# Power.net
KiCad netlist of a schematic drawn in Altium Designer
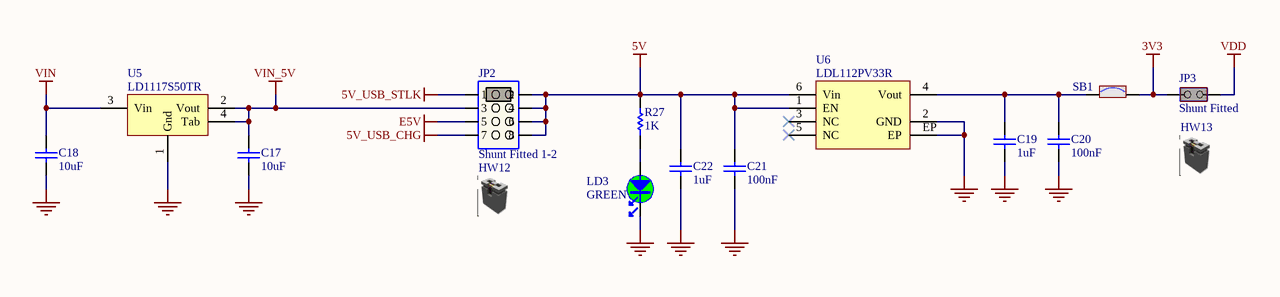
[diagram p0: Power.SchDoc]

(export (version "E")
  (design (tool "Eeschema 10.0.6"))
  (components
    (comp (ref "C17")
      (value "10uF")
      (footprint "C0805")
      (description "Capacitor, MLCC, 10uF, 25V, X5R, 10%, 0805, T=0,85mm")
      (fields
        (field (name "INTERNAL_PART_NUMBER") "MCD-00014")
        (field (name "MANUFACTURER_PART_NUMBER") "CC0805KRX5R8BB106")
        (field (name "PROVIDED_BY") "Subcon")
      )
      (libsource (lib "MCD_PARTS_database") (part "Capacitor"))
    )
    (comp (ref "C18")
      (value "10uF")
      (footprint "C0805")
      (description "Capacitor, MLCC, 10uF, 25V, X5R, 10%, 0805, T=0,85mm")
      (fields
        (field (name "INTERNAL_PART_NUMBER") "MCD-00014")
        (field (name "MANUFACTURER_PART_NUMBER") "CC0805KRX5R8BB106")
        (field (name "PROVIDED_BY") "Subcon")
      )
      (libsource (lib "MCD_PARTS_database") (part "Capacitor"))
    )
    (comp (ref "C19")
      (value "1uF")
      (footprint "C0603")
      (description "Capacitor, MLCC, 1uF, 16V, X5R, 10%, 0603, T=0,8mm")
      (fields
        (field (name "INTERNAL_PART_NUMBER") "MCD-00010")
        (field (name "MANUFACTURER_PART_NUMBER") "CC0603KRX5R7BB105")
        (field (name "PROVIDED_BY") "Subcon")
      )
      (libsource (lib "MCD_PARTS_database") (part "Capacitor"))
    )
    (comp (ref "C20")
      (value "100nF")
      (footprint "C0603")
      (description "Capacitor, MLCC, 100nF, 16V, X7R, 10%, 0603, T=0,8mm")
      (fields
        (field (name "INTERNAL_PART_NUMBER") "MCD-00211")
        (field (name "MANUFACTURER_PART_NUMBER") "CC0603KRX7R7BB104")
        (field (name "PROVIDED_BY") "Subcon")
      )
      (libsource (lib "MCD_PARTS_database") (part "Capacitor"))
    )
    (comp (ref "C21")
      (value "100nF")
      (footprint "C0603")
      (description "Capacitor, MLCC, 100nF, 16V, X7R, 10%, 0603, T=0,8mm")
      (fields
        (field (name "INTERNAL_PART_NUMBER") "MCD-00211")
        (field (name "MANUFACTURER_PART_NUMBER") "CC0603KRX7R7BB104")
        (field (name "PROVIDED_BY") "Subcon")
      )
      (libsource (lib "MCD_PARTS_database") (part "Capacitor"))
    )
    (comp (ref "C22")
      (value "1uF")
      (footprint "C0603")
      (description "Capacitor, MLCC, 1uF, 16V, X5R, 10%, 0603, T=0,8mm")
      (fields
        (field (name "INTERNAL_PART_NUMBER") "MCD-00010")
        (field (name "MANUFACTURER_PART_NUMBER") "CC0603KRX5R7BB105")
        (field (name "PROVIDED_BY") "Subcon")
      )
      (libsource (lib "MCD_PARTS_database") (part "Capacitor"))
    )
    (comp (ref "HW12")
      (value "Shunt 2.54mm")
      (footprint "N/A")
      (description "SHUNT 2.54mm BLACK")
      (fields
        (field (name "INTERNAL_PART_NUMBER") "MCD-00043")
        (field (name "MANUFACTURER_PART_NUMBER") "SNT-100-BK-G")
        (field (name "PROVIDED_BY") "Subcon")
      )
      (libsource (lib "MCD_PARTS_database") (part "Shunt 2.54mm"))
    )
    (comp (ref "HW13")
      (value "Shunt 2.54mm")
      (footprint "N/A")
      (description "SHUNT 2.54mm BLACK")
      (fields
        (field (name "INTERNAL_PART_NUMBER") "MCD-00043")
        (field (name "MANUFACTURER_PART_NUMBER") "SNT-100-BK-G")
        (field (name "PROVIDED_BY") "Subcon")
      )
      (libsource (lib "MCD_PARTS_database") (part "Shunt 2.54mm"))
    )
    (comp (ref "JP2")
      (value "Shunt Fitted 1-2")
      (footprint "CON_SAMTEC_TSW-104-07-X-D")
      (description "Header, 4x2, 2,54mm, VR, TH, Height 5.84mm/2.54mm - Shunt Fitted 1-2")
      (fields
        (field (name "INTERNAL_PART_NUMBER") "MCD-00686")
        (field (name "MANUFACTURER_PART_NUMBER") "TSW-104-07-x-D")
        (field (name "PROVIDED_BY") "Subcon")
      )
      (libsource (lib "MCD_PARTS_database") (part "Jumper_Header 4x2 Fitted 1-2"))
    )
    (comp (ref "JP3")
      (value "Shunt Fitted")
      (footprint "CON_SAMTEC_TSW-102-07-G-S")
      (description "Header, 2x1, 2,54mm, VR, TH, Height 5.84mm/2.54mm - Shunt Fitted by default")
      (fields
        (field (name "INTERNAL_PART_NUMBER") "MCD-00683")
        (field (name "MANUFACTURER_PART_NUMBER") "TSW-102-07-x-S")
        (field (name "PROVIDED_BY") "Subcon")
      )
      (libsource (lib "MCD_PARTS_database") (part "Jumper_Header 2x1 Fitted"))
    )
    (comp (ref "LD3")
      (value "GREEN")
      (footprint "LED_0603_GREEN")
      (description "LED, Green, 0603")
      (fields
        (field (name "INTERNAL_PART_NUMBER") "MCD-00050")
        (field (name "MANUFACTURER_PART_NUMBER") "19-213SYGC/S530-E2/TR8")
        (field (name "PROVIDED_BY") "Subcon")
      )
      (libsource (lib "MCD_PARTS_database") (part "LED_green"))
    )
    (comp (ref "R27")
      (value "1K")
      (footprint "R0603")
      (description "Resistor,1K,0603,1%,1/10W")
      (fields
        (field (name "INTERNAL_PART_NUMBER") "MCD-00070")
        (field (name "MANUFACTURER_PART_NUMBER") "RC0603FR-071KL")
        (field (name "PROVIDED_BY") "Subcon")
      )
      (libsource (lib "MCD_PARTS_database") (part "Resistor"))
    )
    (comp (ref "SB1")
      (value "SB_ON")
      (footprint "SOLDER-BRIDGE_R0603-0R")
      (description "Solder Bridge ON")
      (fields (field (name "INTERNAL_PART_NUMBER") "MCD-00071") (field (name "PROVIDED_BY") "Subcon"))
      (libsource (lib "MCD_PARTS_database") (part "SB_ON"))
    )
    (comp (ref "U5")
      (value "LD1117S50TR")
      (footprint "REG_SOT223-TAB")
      (description "IC REG LDO 5V 0.8A SOT223")
      (fields
        (field (name "INTERNAL_PART_NUMBER") "MCD-00088")
        (field (name "MANUFACTURER") "STMICROELECTRONICS")
        (field (name "PROVIDED_BY") "Subcon")
      )
      (libsource (lib "MCD_PARTS_database") (part "LD1117S50TR"))
    )
    (comp (ref "U6")
      (value "LDL112PV33R")
      (footprint "ICC_DFN6-EPAD_3X3_P095")
      (description "1.2 A low quiescent current LDO with reverse current protection")
      (fields
        (field (name "INTERNAL_PART_NUMBER") "MCD-00664")
        (field (name "MANUFACTURER") "STMICROELECTRONICS")
        (field (name "PROVIDED_BY") "Subcon")
      )
      (libsource (lib "MCD_PARTS_database") (part "LDL112PV33R"))
    )
  )
  (nets
    (net (code "1") (name "3V3") (class "Default")
      (node (ref "JP3") (pin "2") (pinfunction "NO_2") (pintype "passive"))
      (node (ref "SB1") (pin "2") (pinfunction "2_2") (pintype "passive"))
    )
    (net (code "2") (name "5V") (class "Default")
      (node (ref "C21") (pin "2") (pinfunction "2_2") (pintype "passive"))
      (node (ref "C22") (pin "2") (pinfunction "2_2") (pintype "passive"))
      (node (ref "JP2") (pin "2") (pinfunction "2_2") (pintype "passive"))
      (node (ref "JP2") (pin "4") (pinfunction "4_4") (pintype "passive"))
      (node (ref "JP2") (pin "6") (pinfunction "6_6") (pintype "passive"))
      (node (ref "JP2") (pin "8") (pinfunction "8_8") (pintype "passive"))
      (node (ref "R27") (pin "1") (pinfunction "1_1") (pintype "passive"))
      (node (ref "U6") (pin "1") (pinfunction "EN_1") (pintype "passive"))
      (node (ref "U6") (pin "6") (pinfunction "Vin_6") (pintype "passive"))
    )
    (net (code "3") (name "5V_USB_CHG") (class "Default")
      (node (ref "JP2") (pin "7") (pinfunction "7_7") (pintype "passive"))
    )
    (net (code "4") (name "5V_USB_STLK") (class "Default")
      (node (ref "JP2") (pin "1") (pinfunction "1_1") (pintype "passive"))
    )
    (net (code "5") (name "E5V") (class "Default")
      (node (ref "JP2") (pin "5") (pinfunction "5_5") (pintype "passive"))
    )
    (net (code "6") (name "GND") (class "Default")
      (node (ref "C17") (pin "1") (pinfunction "1_1") (pintype "passive"))
      (node (ref "C18") (pin "1") (pinfunction "1_1") (pintype "passive"))
      (node (ref "C19") (pin "1") (pinfunction "1_1") (pintype "passive"))
      (node (ref "C20") (pin "1") (pinfunction "1_1") (pintype "passive"))
      (node (ref "C21") (pin "1") (pinfunction "1_1") (pintype "passive"))
      (node (ref "C22") (pin "1") (pinfunction "1_1") (pintype "passive"))
      (node (ref "LD3") (pin "2") (pintype "passive"))
      (node (ref "U5") (pin "1") (pinfunction "Gnd_1") (pintype "passive"))
      (node (ref "U6") (pin "2") (pinfunction "GND_2") (pintype "passive"))
      (node (ref "U6") (pin "EP") (pinfunction "EP_EP") (pintype "passive"))
    )
    (net (code "7") (name "Net-(LD3-Pad1)") (class "Default")
      (node (ref "LD3") (pin "1") (pintype "passive"))
      (node (ref "R27") (pin "2") (pinfunction "2_2") (pintype "passive"))
    )
    (net (code "8") (name "Net-(U6-Vout)") (class "Default")
      (node (ref "C19") (pin "2") (pinfunction "2_2") (pintype "passive"))
      (node (ref "C20") (pin "2") (pinfunction "2_2") (pintype "passive"))
      (node (ref "SB1") (pin "1") (pinfunction "1_1") (pintype "passive"))
      (node (ref "U6") (pin "4") (pinfunction "Vout_4") (pintype "passive"))
    )
    (net (code "9") (name "VDD") (class "Default")
      (node (ref "JP3") (pin "1") (pinfunction "COMMON_1") (pintype "passive"))
    )
    (net (code "10") (name "VIN") (class "Default")
      (node (ref "C18") (pin "2") (pinfunction "2_2") (pintype "passive"))
      (node (ref "U5") (pin "3") (pinfunction "Vin_3") (pintype "passive"))
    )
    (net (code "11") (name "VIN_5V") (class "Default")
      (node (ref "C17") (pin "2") (pinfunction "2_2") (pintype "passive"))
      (node (ref "JP2") (pin "3") (pinfunction "3_3") (pintype "passive"))
      (node (ref "U5") (pin "2") (pinfunction "Vout_2") (pintype "passive"))
      (node (ref "U5") (pin "4") (pinfunction "Tab_4") (pintype "passive"))
    )
    (net (code "12") (name "unconnected-(U6-NC-Pad3)") (class "Default")
      (node (ref "U6") (pin "3") (pinfunction "NC_3") (pintype "passive+no_connect"))
    )
    (net (code "13") (name "unconnected-(U6-NC-Pad5)") (class "Default")
      (node (ref "U6") (pin "5") (pinfunction "NC_5") (pintype "passive+no_connect"))
    )
  )
)
